# MyRollerShutter_rfm.net
KiCad netlist of a schematic drawn in EAGLE
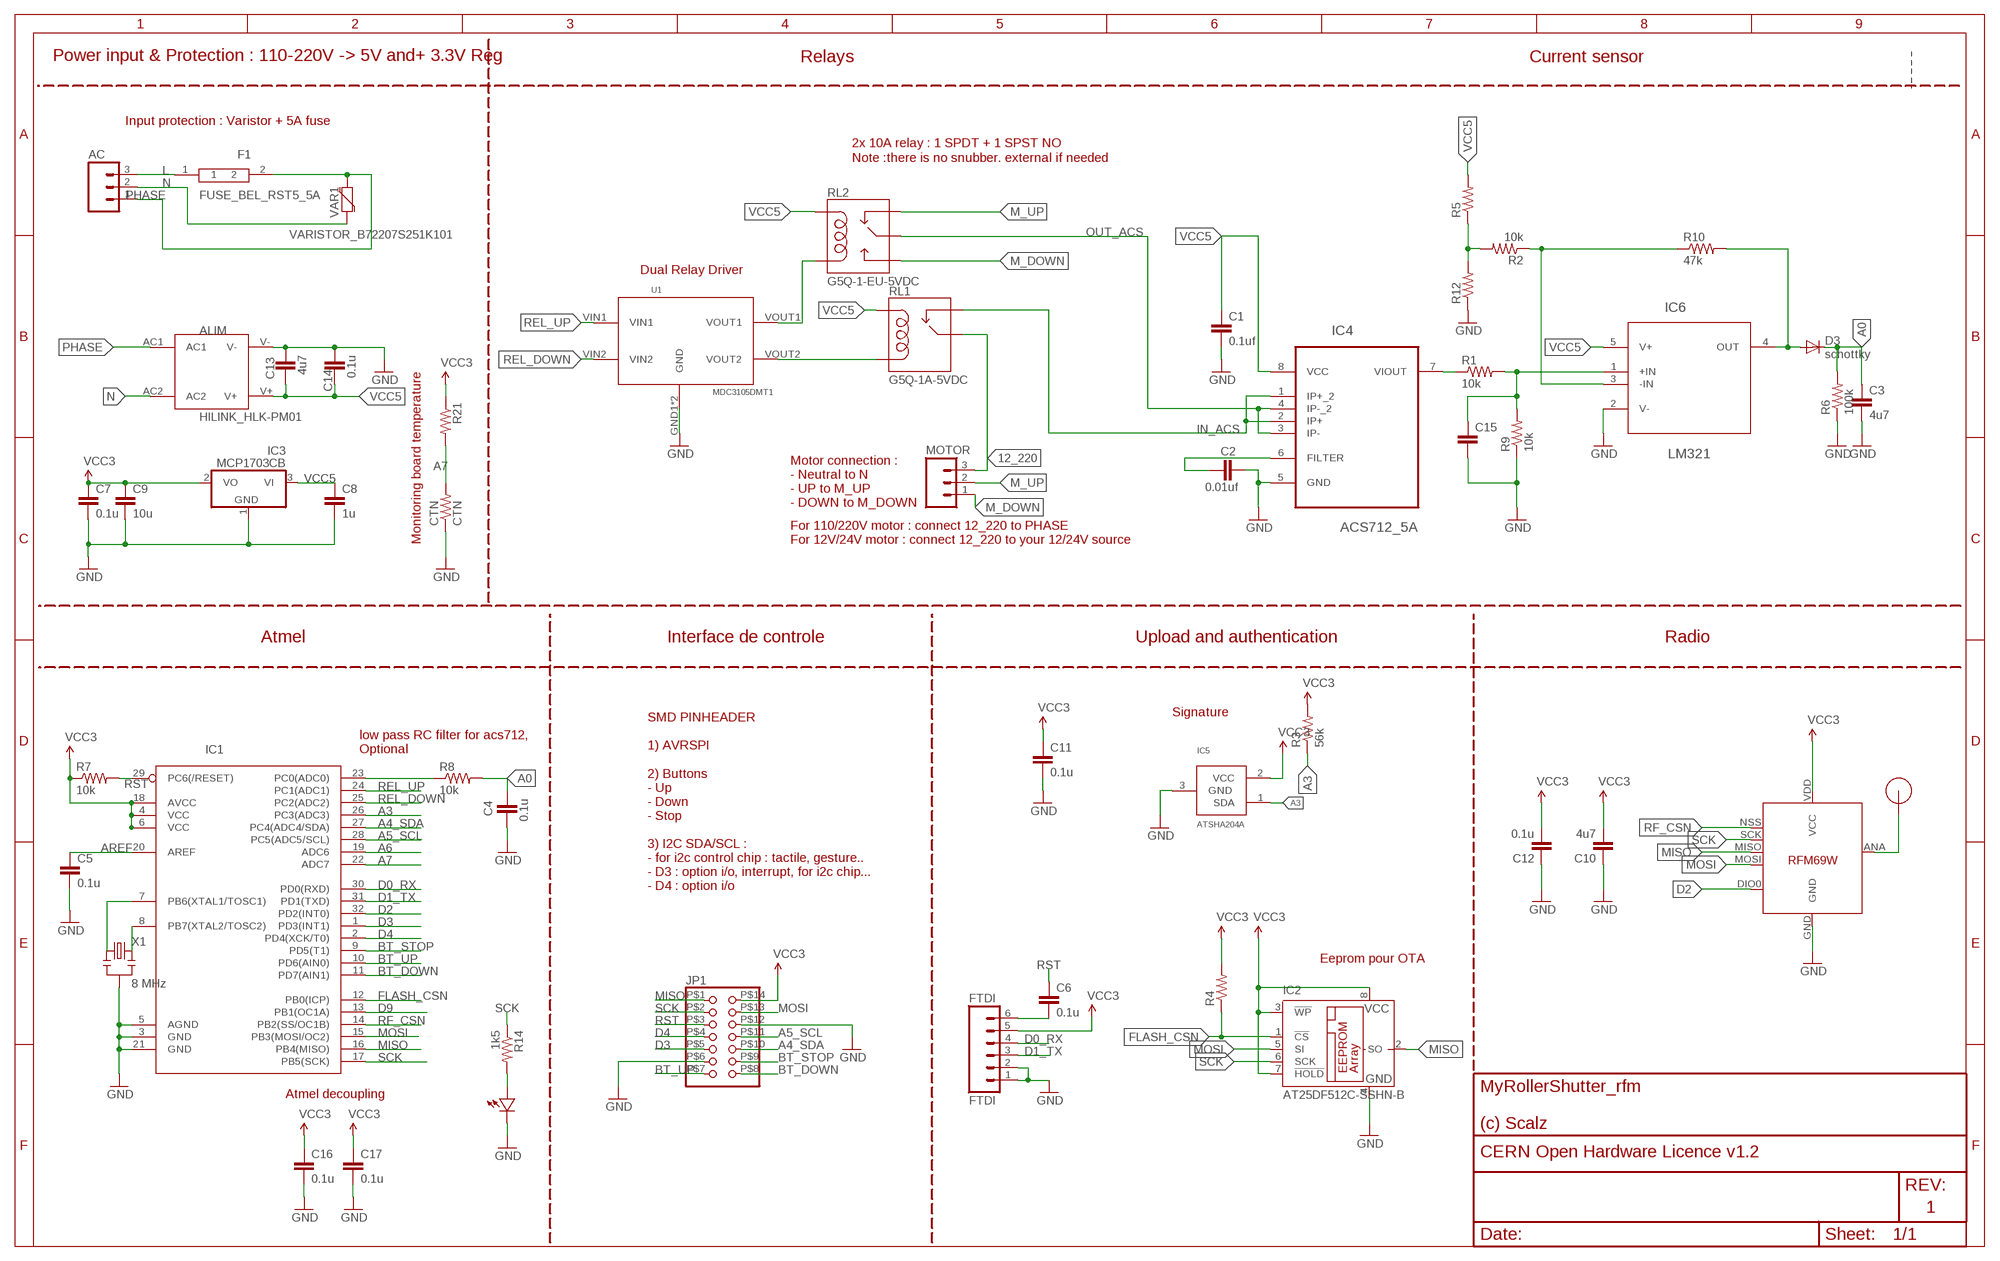
[diagram p0: schematic, sheet 1]

(export (version "E")
  (design (tool "Eeschema 10.0.6"))
  (components
    (comp (ref "AC")
      (value "M03-SCREW-5MM")
      (footprint "eagle-import:SCREWTERMINAL-5MM-3")
      (libsource (lib "eagle-import") (part "M03-SCREW-5MM"))
    )
    (comp (ref "ALIM")
      (value "HILINK_HLK-PM01")
      (footprint "eagle-import:HILINK_HLK-PM01")
      (libsource (lib "eagle-import") (part "HILINK_HLK-PM01"))
    )
    (comp (ref "ANT")
      (value "RFM12B_ANTENNA")
      (footprint "eagle-import:RFM12B-ANTENNA")
      (libsource (lib "eagle-import") (part "RFM12B_ANTENNA"))
    )
    (comp (ref "C1")
      (value "0.1uf")
      (footprint "eagle-import:0805-CAP")
      (libsource (lib "eagle-import") (part "CAP0805-CAP"))
    )
    (comp (ref "C2")
      (value "0.01uf")
      (footprint "eagle-import:0805-CAP")
      (libsource (lib "eagle-import") (part "CAP0805-CAP"))
    )
    (comp (ref "C3")
      (value "4u7")
      (footprint "eagle-import:0805-CAP")
      (libsource (lib "eagle-import") (part "CAP0805-CAP"))
    )
    (comp (ref "C4")
      (value "0.1u")
      (footprint "eagle-import:0805-CAP")
      (libsource (lib "eagle-import") (part "CAP0805-CAP"))
    )
    (comp (ref "C5")
      (value "0.1u")
      (footprint "eagle-import:0805-CAP")
      (libsource (lib "eagle-import") (part "CAP0805-CAP"))
    )
    (comp (ref "C6")
      (value "0.1u")
      (footprint "eagle-import:0805-CAP")
      (libsource (lib "eagle-import") (part "CAP0805-CAP"))
    )
    (comp (ref "C7")
      (value "0.1u")
      (footprint "eagle-import:0805-CAP")
      (libsource (lib "eagle-import") (part "CAP0805-CAP"))
    )
    (comp (ref "C8")
      (value "1u")
      (footprint "eagle-import:0805-CAP")
      (libsource (lib "eagle-import") (part "CAP0805-CAP"))
    )
    (comp (ref "C9")
      (value "10u")
      (footprint "eagle-import:0805-CAP")
      (libsource (lib "eagle-import") (part "CAP0805-CAP"))
    )
    (comp (ref "C10")
      (value "4u7")
      (footprint "eagle-import:0805-CAP")
      (libsource (lib "eagle-import") (part "CAP0805-CAP"))
    )
    (comp (ref "C11")
      (value "0.1u")
      (footprint "eagle-import:0805-CAP")
      (libsource (lib "eagle-import") (part "CAP0805-CAP"))
    )
    (comp (ref "C12")
      (value "0.1u")
      (footprint "eagle-import:0805-CAP")
      (libsource (lib "eagle-import") (part "CAP0805-CAP"))
    )
    (comp (ref "C13")
      (value "4u7")
      (footprint "eagle-import:0805-CAP")
      (libsource (lib "eagle-import") (part "CAP0805-CAP"))
    )
    (comp (ref "C14")
      (value "0.1u")
      (footprint "eagle-import:0805-CAP")
      (libsource (lib "eagle-import") (part "CAP0805-CAP"))
    )
    (comp (ref "C15")
      (value "CAP0805-CAP")
      (footprint "eagle-import:0805-CAP")
      (libsource (lib "eagle-import") (part "CAP0805-CAP"))
    )
    (comp (ref "C16")
      (value "0.1u")
      (footprint "eagle-import:0805-CAP")
      (libsource (lib "eagle-import") (part "CAP0805-CAP"))
    )
    (comp (ref "C17")
      (value "0.1u")
      (footprint "eagle-import:0805-CAP")
      (libsource (lib "eagle-import") (part "CAP0805-CAP"))
    )
    (comp (ref "CTN")
      (value "CTN")
      (footprint "eagle-import:0805-RES")
      (libsource (lib "eagle-import") (part "RESISTOR0805-RES"))
    )
    (comp (ref "D3")
      (value "schottky")
      (footprint "eagle-import:SOD-323")
      (libsource (lib "eagle-import") (part "DIODESOD"))
    )
    (comp (ref "D4")
      (value "LED0805")
      (footprint "eagle-import:0805-LED")
      (libsource (lib "eagle-import") (part "LED0805"))
    )
    (comp (ref "F1")
      (value "FUSE_BEL_RST5_5A")
      (footprint "eagle-import:FUSE_BEL_RST5_5A")
      (libsource (lib "eagle-import") (part "FUSE_BEL_RST5_5A"))
    )
    (comp (ref "FTDI")
      (value "FTDI")
      (footprint "eagle-import:1X06")
      (libsource (lib "eagle-import") (part "M06SIP"))
    )
    (comp (ref "IC1")
      (value "ATMega-328")
      (footprint "eagle-import:TQFP32-08")
      (libsource (lib "eagle-import") (part "ATMEGA168/328TQFP32"))
    )
    (comp (ref "IC2")
      (value "AT25DF512C-SSHN-B")
      (footprint "eagle-import:SO-08")
      (fields (field (name "MF") "MICROCHIP") (field (name "MPN") "25AA080/SN"))
      (libsource (lib "eagle-import") (part "25SNAA080"))
    )
    (comp (ref "IC3")
      (value "MCP1703CB")
      (footprint "eagle-import:SOT23")
      (libsource (lib "eagle-import") (part "MCP1703CB"))
    )
    (comp (ref "IC4")
      (value "ACS712_5A")
      (footprint "eagle-import:SOIC127P600X175-8N")
      (fields (field (name "MPN") "ACS712ELCTR-20A-T"))
      (libsource (lib "eagle-import") (part "ACS712ELCTR-20A-T"))
    )
    (comp (ref "IC5")
      (value "ATSHA204A")
      (footprint "eagle-import:SOT23")
      (libsource (lib "eagle-import") (part "ATSHA204A"))
    )
    (comp (ref "IC6")
      (value "LM321")
      (footprint "eagle-import:SOT95P285X120-5N")
      (fields (field (name "MPN") "LM321MF"))
      (libsource (lib "eagle-import") (part "LM321MF"))
    )
    (comp (ref "JP1")
      (value "PINHD-2X7")
      (footprint "eagle-import:2X07")
      (libsource (lib "eagle-import") (part "PINHD-2X7"))
    )
    (comp (ref "MOTOR")
      (value "M03-SCREW-5MM")
      (footprint "eagle-import:SCREWTERMINAL-5MM-3")
      (libsource (lib "eagle-import") (part "M03-SCREW-5MM"))
    )
    (comp (ref "R1")
      (value "10k")
      (footprint "eagle-import:0805-RES")
      (libsource (lib "eagle-import") (part "RESISTOR0805-RES"))
    )
    (comp (ref "R2")
      (value "10k")
      (footprint "eagle-import:0805-RES")
      (libsource (lib "eagle-import") (part "RESISTOR0805-RES"))
    )
    (comp (ref "R3")
      (value "56k")
      (footprint "eagle-import:0805-RES")
      (libsource (lib "eagle-import") (part "RESISTOR0805-RES"))
    )
    (comp (ref "R4")
      (value "RESISTOR0805-RES")
      (footprint "eagle-import:0805-RES")
      (libsource (lib "eagle-import") (part "RESISTOR0805-RES"))
    )
    (comp (ref "R5")
      (value "RESISTOR0805-RES")
      (footprint "eagle-import:0805-RES")
      (libsource (lib "eagle-import") (part "RESISTOR0805-RES"))
    )
    (comp (ref "R6")
      (value "100k")
      (footprint "eagle-import:0805-RES")
      (libsource (lib "eagle-import") (part "RESISTOR0805-RES"))
    )
    (comp (ref "R7")
      (value "10k")
      (footprint "eagle-import:0805-RES")
      (libsource (lib "eagle-import") (part "RESISTOR0805-RES"))
    )
    (comp (ref "R8")
      (value "10k")
      (footprint "eagle-import:0805-RES")
      (libsource (lib "eagle-import") (part "RESISTOR0805-RES"))
    )
    (comp (ref "R9")
      (value "10k")
      (footprint "eagle-import:0805-RES")
      (libsource (lib "eagle-import") (part "RESISTOR0805-RES"))
    )
    (comp (ref "R10")
      (value "47k")
      (footprint "eagle-import:0805-RES")
      (libsource (lib "eagle-import") (part "RESISTOR0805-RES"))
    )
    (comp (ref "R12")
      (value "RESISTOR0805-RES")
      (footprint "eagle-import:0805-RES")
      (libsource (lib "eagle-import") (part "RESISTOR0805-RES"))
    )
    (comp (ref "R14")
      (value "1k5")
      (footprint "eagle-import:0805-RES")
      (libsource (lib "eagle-import") (part "RESISTOR0805-RES"))
    )
    (comp (ref "R21")
      (value "RESISTOR0805-RES")
      (footprint "eagle-import:0805-RES")
      (libsource (lib "eagle-import") (part "RESISTOR0805-RES"))
    )
    (comp (ref "RFM69")
      (value "RFM69")
      (footprint "eagle-import:RFM69W-MINPADS")
      (libsource (lib "eagle-import") (part "RFM69"))
    )
    (comp (ref "RL1")
      (value "G5Q-1A-5VDC")
      (footprint "eagle-import:G5Q_SINGLE")
      (libsource (lib "eagle-import") (part "G5Q_SINGLE"))
    )
    (comp (ref "RL2")
      (value "G5Q-1-EU-5VDC")
      (footprint "eagle-import:RELAY-G5Q")
      (libsource (lib "eagle-import") (part "RELAYPTH"))
    )
    (comp (ref "U1")
      (value "MDC3105DMT1")
      (footprint "eagle-import:MDC3105DMT1")
      (libsource (lib "eagle-import") (part "MDC3105DMT1"))
    )
    (comp (ref "VAR1")
      (value "VARISTOR_B72207S251K101")
      (footprint "eagle-import:VARISTOR_B72207S251K101")
      (libsource (lib "eagle-import") (part "VARISTOR_B72207S251K101"))
    )
    (comp (ref "X1")
      (value "8 MHz")
      (footprint "eagle-import:RESONATOR-SMD")
      (libsource (lib "eagle-import") (part "RESONATORSMD"))
    )
  )
  (nets
    (net (code "1") (name "/A4_SDA") (class "Default")
      (node (ref "IC1") (pin "27") (pinfunction "PC4(ADC4/SDA)_27") (pintype "bidirectional"))
      (node (ref "JP1") (pin "P$10") (pinfunction "10_P$10") (pintype "passive"))
    )
    (net (code "2") (name "/A5_SCL") (class "Default")
      (node (ref "IC1") (pin "28") (pinfunction "PC5(ADC5/SCL)_28") (pintype "bidirectional"))
      (node (ref "JP1") (pin "P$11") (pinfunction "8_P$11") (pintype "passive"))
    )
    (net (code "3") (name "/A6") (class "Default")
      (node (ref "IC1") (pin "19") (pinfunction "ADC6_19") (pintype "bidirectional"))
    )
    (net (code "4") (name "/A7") (class "Default")
      (node (ref "CTN") (pin "2") (pinfunction "2_2") (pintype "passive"))
      (node (ref "IC1") (pin "22") (pinfunction "ADC7_22") (pintype "bidirectional"))
      (node (ref "R21") (pin "2") (pinfunction "2_2") (pintype "passive"))
    )
    (net (code "5") (name "/AREF") (class "Default")
      (node (ref "C5") (pin "1") (pinfunction "1_1") (pintype "passive"))
      (node (ref "IC1") (pin "20") (pinfunction "AREF_20") (pintype "bidirectional"))
    )
    (net (code "6") (name "/BT_DOWN") (class "Default")
      (node (ref "IC1") (pin "11") (pinfunction "PD7(AIN1)_11") (pintype "bidirectional"))
      (node (ref "JP1") (pin "P$8") (pinfunction "14_P$8") (pintype "passive"))
    )
    (net (code "7") (name "/BT_STOP") (class "Default")
      (node (ref "IC1") (pin "9") (pinfunction "PD5(T1)_9") (pintype "bidirectional"))
      (node (ref "JP1") (pin "P$9") (pinfunction "12_P$9") (pintype "passive"))
    )
    (net (code "8") (name "/BT_UP") (class "Default")
      (node (ref "IC1") (pin "10") (pinfunction "PD6(AIN0)_10") (pintype "bidirectional"))
      (node (ref "JP1") (pin "P$7") (pinfunction "13_P$7") (pintype "passive"))
    )
    (net (code "9") (name "/D0_RX") (class "Default")
      (node (ref "FTDI") (pin "4") (pinfunction "4_4") (pintype "passive"))
      (node (ref "IC1") (pin "30") (pinfunction "PD0(RXD)_30") (pintype "bidirectional"))
    )
    (net (code "10") (name "/D1_TX") (class "Default")
      (node (ref "FTDI") (pin "3") (pinfunction "3_3") (pintype "passive"))
      (node (ref "IC1") (pin "31") (pinfunction "PD1(TXD)_31") (pintype "bidirectional"))
    )
    (net (code "11") (name "/D3") (class "Default")
      (node (ref "IC1") (pin "1") (pinfunction "PD3(INT1)_1") (pintype "bidirectional"))
      (node (ref "JP1") (pin "P$5") (pinfunction "9_P$5") (pintype "passive"))
    )
    (net (code "12") (name "/D4") (class "Default")
      (node (ref "IC1") (pin "2") (pinfunction "PD4(XCK/T0)_2") (pintype "bidirectional"))
      (node (ref "JP1") (pin "P$4") (pinfunction "7_P$4") (pintype "passive"))
    )
    (net (code "13") (name "/D9") (class "Default")
      (node (ref "IC1") (pin "13") (pinfunction "PB1(OC1A)_13") (pintype "bidirectional"))
    )
    (net (code "14") (name "/IN_ACS") (class "Default")
      (node (ref "IC4") (pin "1") (pinfunction "IP+_2_1") (pintype "input"))
      (node (ref "IC4") (pin "2") (pinfunction "IP+_2") (pintype "input"))
      (node (ref "RL1") (pin "3") (pinfunction "NC_3") (pintype "bidirectional"))
    )
    (net (code "15") (name "/L") (class "Default")
      (node (ref "AC") (pin "3") (pinfunction "3_3") (pintype "passive"))
      (node (ref "F1") (pin "1") (pinfunction "1_1") (pintype "bidirectional"))
    )
    (net (code "16") (name "/OUT_ACS") (class "Default")
      (node (ref "IC4") (pin "3") (pinfunction "IP-_3") (pintype "input"))
      (node (ref "IC4") (pin "4") (pinfunction "IP-_2_4") (pintype "input"))
      (node (ref "RL2") (pin "2") (pinfunction "MAIN_2") (pintype "bidirectional"))
    )
    (net (code "17") (name "/RST") (class "Default")
      (node (ref "C6") (pin "1") (pinfunction "1_1") (pintype "passive"))
      (node (ref "IC1") (pin "29") (pinfunction "PC6(/RESET)_29") (pintype "bidirectional"))
      (node (ref "JP1") (pin "P$3") (pinfunction "5_P$3") (pintype "passive"))
      (node (ref "R7") (pin "2") (pinfunction "2_2") (pintype "passive"))
    )
    (net (code "18") (name "12_220") (class "Default")
      (node (ref "MOTOR") (pin "3") (pinfunction "3_3") (pintype "passive"))
      (node (ref "RL1") (pin "2") (pinfunction "MAIN_2") (pintype "bidirectional"))
    )
    (net (code "19") (name "A0") (class "Default")
      (node (ref "C3") (pin "1") (pinfunction "1_1") (pintype "passive"))
      (node (ref "C4") (pin "2") (pinfunction "2_2") (pintype "passive"))
      (node (ref "D3") (pin "1") (pinfunction "C_1") (pintype "passive"))
      (node (ref "R6") (pin "2") (pinfunction "2_2") (pintype "passive"))
      (node (ref "R8") (pin "2") (pinfunction "2_2") (pintype "passive"))
    )
    (net (code "20") (name "A3") (class "Default")
      (node (ref "IC1") (pin "26") (pinfunction "PC3(ADC3)_26") (pintype "bidirectional"))
      (node (ref "IC5") (pin "1") (pinfunction "SDA_1") (pintype "bidirectional"))
      (node (ref "R3") (pin "1") (pinfunction "1_1") (pintype "passive"))
    )
    (net (code "21") (name "D2") (class "Default")
      (node (ref "IC1") (pin "32") (pinfunction "PD2(INT0)_32") (pintype "bidirectional"))
      (node (ref "RFM69") (pin "DIO0") (pinfunction "DIO0_DIO0") (pintype "open_collector"))
    )
    (net (code "22") (name "FLASH_CSN") (class "Default")
      (node (ref "IC1") (pin "12") (pinfunction "PB0(ICP)_12") (pintype "bidirectional"))
      (node (ref "IC2") (pin "1") (pinfunction "~{CS}_1") (pintype "input"))
      (node (ref "R4") (pin "1") (pinfunction "1_1") (pintype "passive"))
    )
    (net (code "23") (name "GND") (class "Default")
      (node (ref "ALIM") (pin "V-") (pinfunction "V-_V-") (pintype "bidirectional"))
      (node (ref "C1") (pin "2") (pinfunction "2_2") (pintype "passive"))
      (node (ref "C10") (pin "1") (pinfunction "1_1") (pintype "passive"))
      (node (ref "C11") (pin "2") (pinfunction "2_2") (pintype "passive"))
      (node (ref "C12") (pin "1") (pinfunction "1_1") (pintype "passive"))
      (node (ref "C13") (pin "2") (pinfunction "2_2") (pintype "passive"))
      (node (ref "C14") (pin "2") (pinfunction "2_2") (pintype "passive"))
      (node (ref "C15") (pin "2") (pinfunction "2_2") (pintype "passive"))
      (node (ref "C16") (pin "2") (pinfunction "2_2") (pintype "passive"))
      (node (ref "C17") (pin "2") (pinfunction "2_2") (pintype "passive"))
      (node (ref "C2") (pin "2") (pinfunction "2_2") (pintype "passive"))
      (node (ref "C3") (pin "2") (pinfunction "2_2") (pintype "passive"))
      (node (ref "C4") (pin "1") (pinfunction "1_1") (pintype "passive"))
      (node (ref "C5") (pin "2") (pinfunction "2_2") (pintype "passive"))
      (node (ref "C7") (pin "2") (pinfunction "2_2") (pintype "passive"))
      (node (ref "C8") (pin "2") (pinfunction "2_2") (pintype "passive"))
      (node (ref "C9") (pin "2") (pinfunction "2_2") (pintype "passive"))
      (node (ref "CTN") (pin "1") (pinfunction "1_1") (pintype "passive"))
      (node (ref "D4") (pin "MINUS") (pinfunction "MINUS_MINUS") (pintype "passive"))
      (node (ref "FTDI") (pin "1") (pinfunction "1_1") (pintype "passive"))
      (node (ref "FTDI") (pin "2") (pinfunction "2_2") (pintype "passive"))
      (node (ref "IC1") (pin "21") (pinfunction "GND_21") (pintype "bidirectional"))
      (node (ref "IC1") (pin "3") (pinfunction "GND_3") (pintype "bidirectional"))
      (node (ref "IC1") (pin "5") (pinfunction "AGND_5") (pintype "bidirectional"))
      (node (ref "IC2") (pin "4") (pinfunction "GND_4") (pintype "power_in"))
      (node (ref "IC3") (pin "1") (pinfunction "GND_1") (pintype "passive"))
      (node (ref "IC4") (pin "5") (pinfunction "GND_5") (pintype "passive"))
      (node (ref "IC5") (pin "3") (pinfunction "GND_3") (pintype "bidirectional"))
      (node (ref "IC6") (pin "2") (pinfunction "V-_2") (pintype "power_in"))
      (node (ref "JP1") (pin "P$12") (pinfunction "6_P$12") (pintype "passive"))
      (node (ref "JP1") (pin "P$6") (pinfunction "11_P$6") (pintype "passive"))
      (node (ref "R12") (pin "1") (pinfunction "1_1") (pintype "passive"))
      (node (ref "R6") (pin "1") (pinfunction "1_1") (pintype "passive"))
      (node (ref "R9") (pin "1") (pinfunction "1_1") (pintype "passive"))
      (node (ref "RFM69") (pin "GND") (pinfunction "GND_GND") (pintype "power_in"))
      (node (ref "U1") (pin "GND1") (pinfunction "GND_GND1") (pintype "bidirectional"))
      (node (ref "U1") (pin "GND2") (pinfunction "GND_GND2") (pintype "bidirectional"))
      (node (ref "X1") (pin "2") (pinfunction "2_2") (pintype "passive"))
    )
    (net (code "24") (name "MISO") (class "Default")
      (node (ref "IC1") (pin "16") (pinfunction "PB4(MISO)_16") (pintype "bidirectional"))
      (node (ref "IC2") (pin "2") (pinfunction "SO_2") (pintype "bidirectional"))
      (node (ref "JP1") (pin "P$1") (pinfunction "1_P$1") (pintype "passive"))
      (node (ref "RFM69") (pin "MISO") (pinfunction "MISO_MISO") (pintype "input"))
    )
    (net (code "25") (name "MOSI") (class "Default")
      (node (ref "IC1") (pin "15") (pinfunction "PB3(MOSI/OC2)_15") (pintype "bidirectional"))
      (node (ref "IC2") (pin "5") (pinfunction "SI_5") (pintype "input"))
      (node (ref "JP1") (pin "P$13") (pinfunction "4_P$13") (pintype "passive"))
      (node (ref "RFM69") (pin "MOSI") (pinfunction "MOSI_MOSI") (pintype "output"))
    )
    (net (code "26") (name "M_DOWN") (class "Default")
      (node (ref "MOTOR") (pin "1") (pinfunction "1_1") (pintype "passive"))
      (node (ref "RL2") (pin "3") (pinfunction "NO_3") (pintype "bidirectional"))
    )
    (net (code "27") (name "M_UP") (class "Default")
      (node (ref "MOTOR") (pin "2") (pinfunction "2_2") (pintype "passive"))
      (node (ref "RL2") (pin "4") (pinfunction "NC_4") (pintype "bidirectional"))
    )
    (net (code "28") (name "N") (class "Default")
      (node (ref "AC") (pin "2") (pinfunction "2_2") (pintype "passive"))
      (node (ref "ALIM") (pin "AC2") (pinfunction "AC2_AC2") (pintype "bidirectional"))
      (node (ref "VAR1") (pin "1") (pinfunction "1_1") (pintype "passive"))
    )
    (net (code "29") (name "Net-(ANT-1)") (class "Default")
      (node (ref "ANT") (pin "P$1") (pinfunction "1_P$1") (pintype "bidirectional"))
      (node (ref "RFM69") (pin "ANA") (pinfunction "ANT_ANA") (pintype "passive"))
    )
    (net (code "30") (name "Net-(C6-Pad2)") (class "Default")
      (node (ref "C6") (pin "2") (pinfunction "2_2") (pintype "passive"))
      (node (ref "FTDI") (pin "6") (pinfunction "6_6") (pintype "passive"))
    )
    (net (code "31") (name "Net-(D3-A)") (class "Default")
      (node (ref "D3") (pin "2") (pinfunction "A_2") (pintype "passive"))
      (node (ref "IC6") (pin "4") (pinfunction "OUT_4") (pintype "output"))
      (node (ref "R10") (pin "2") (pinfunction "2_2") (pintype "passive"))
    )
    (net (code "32") (name "Net-(D4-PadPLUS)") (class "Default")
      (node (ref "D4") (pin "PLUS") (pinfunction "PLUS_PLUS") (pintype "passive"))
      (node (ref "R14") (pin "2") (pinfunction "2_2") (pintype "passive"))
    )
    (net (code "33") (name "Net-(IC1-PB6(XTAL1{slash}TOSC1))") (class "Default")
      (node (ref "IC1") (pin "7") (pinfunction "PB6(XTAL1/TOSC1)_7") (pintype "bidirectional"))
      (node (ref "X1") (pin "1") (pinfunction "1_1") (pintype "passive"))
    )
    (net (code "34") (name "Net-(IC1-PB7(XTAL2{slash}TOSC2))") (class "Default")
      (node (ref "IC1") (pin "8") (pinfunction "PB7(XTAL2/TOSC2)_8") (pintype "bidirectional"))
      (node (ref "X1") (pin "3") (pinfunction "3_3") (pintype "passive"))
    )
    (net (code "35") (name "Net-(IC1-PC0(ADC0))") (class "Default")
      (node (ref "IC1") (pin "23") (pinfunction "PC0(ADC0)_23") (pintype "bidirectional"))
      (node (ref "R8") (pin "1") (pinfunction "1_1") (pintype "passive"))
    )
    (net (code "36") (name "Net-(IC4-FILTER)") (class "Default")
      (node (ref "C2") (pin "1") (pinfunction "1_1") (pintype "passive"))
      (node (ref "IC4") (pin "6") (pinfunction "FILTER_6") (pintype "input"))
    )
    (net (code "37") (name "Net-(IC4-VIOUT)") (class "Default")
      (node (ref "IC4") (pin "7") (pinfunction "VIOUT_7") (pintype "output"))
      (node (ref "R1") (pin "1") (pinfunction "1_1") (pintype "passive"))
    )
    (net (code "38") (name "Net-(IC6-+IN)") (class "Default")
      (node (ref "C15") (pin "1") (pinfunction "1_1") (pintype "passive"))
      (node (ref "IC6") (pin "1") (pinfunction "+IN_1") (pintype "input"))
      (node (ref "R1") (pin "2") (pinfunction "2_2") (pintype "passive"))
      (node (ref "R9") (pin "2") (pinfunction "2_2") (pintype "passive"))
    )
    (net (code "39") (name "Net-(IC6--IN)") (class "Default")
      (node (ref "IC6") (pin "3") (pinfunction "-IN_3") (pintype "input"))
      (node (ref "R10") (pin "1") (pinfunction "1_1") (pintype "passive"))
      (node (ref "R2") (pin "1") (pinfunction "1_1") (pintype "passive"))
    )
    (net (code "40") (name "Net-(R12-Pad2)") (class "Default")
      (node (ref "R12") (pin "2") (pinfunction "2_2") (pintype "passive"))
      (node (ref "R2") (pin "2") (pinfunction "2_2") (pintype "passive"))
      (node (ref "R5") (pin "1") (pinfunction "1_1") (pintype "passive"))
    )
    (net (code "41") (name "Net-(RL1-COIL2)") (class "Default")
      (node (ref "RL1") (pin "5") (pinfunction "COIL2_5") (pintype "bidirectional"))
      (node (ref "U1") (pin "VOUT2") (pinfunction "VOUT2_VOUT2") (pintype "bidirectional"))
    )
    (net (code "42") (name "Net-(RL2-COIL2)") (class "Default")
      (node (ref "RL2") (pin "1") (pinfunction "COIL2_1") (pintype "bidirectional"))
      (node (ref "U1") (pin "VOUT1") (pinfunction "VOUT1_VOUT1") (pintype "bidirectional"))
    )
    (net (code "43") (name "PHASE") (class "Default")
      (node (ref "AC") (pin "1") (pinfunction "1_1") (pintype "passive"))
      (node (ref "ALIM") (pin "AC1") (pinfunction "AC1_AC1") (pintype "bidirectional"))
      (node (ref "F1") (pin "2") (pinfunction "2_2") (pintype "bidirectional"))
      (node (ref "VAR1") (pin "2") (pinfunction "2_2") (pintype "passive"))
    )
    (net (code "44") (name "REL_DOWN") (class "Default")
      (node (ref "IC1") (pin "25") (pinfunction "PC2(ADC2)_25") (pintype "bidirectional"))
      (node (ref "U1") (pin "VIN2") (pinfunction "VIN2_VIN2") (pintype "bidirectional"))
    )
    (net (code "45") (name "REL_UP") (class "Default")
      (node (ref "IC1") (pin "24") (pinfunction "PC1(ADC1)_24") (pintype "bidirectional"))
      (node (ref "U1") (pin "VIN1") (pinfunction "VIN1_VIN1") (pintype "bidirectional"))
    )
    (net (code "46") (name "RF_CSN") (class "Default")
      (node (ref "IC1") (pin "14") (pinfunction "PB2(SS/OC1B)_14") (pintype "bidirectional"))
      (node (ref "RFM69") (pin "NSS") (pinfunction "SEL_NSS") (pintype "input"))
    )
    (net (code "47") (name "SCK") (class "Default")
      (node (ref "IC1") (pin "17") (pinfunction "PB5(SCK)_17") (pintype "bidirectional"))
      (node (ref "IC2") (pin "6") (pinfunction "SCK_6") (pintype "input"))
      (node (ref "JP1") (pin "P$2") (pinfunction "3_P$2") (pintype "passive"))
      (node (ref "R14") (pin "1") (pinfunction "1_1") (pintype "passive"))
      (node (ref "RFM69") (pin "SCK") (pinfunction "SCK_SCK") (pintype "input"))
    )
    (net (code "48") (name "VCC3") (class "Default")
      (node (ref "C10") (pin "2") (pinfunction "2_2") (pintype "passive"))
      (node (ref "C11") (pin "1") (pinfunction "1_1") (pintype "passive"))
      (node (ref "C12") (pin "2") (pinfunction "2_2") (pintype "passive"))
      (node (ref "C16") (pin "1") (pinfunction "1_1") (pintype "passive"))
      (node (ref "C17") (pin "1") (pinfunction "1_1") (pintype "passive"))
      (node (ref "C7") (pin "1") (pinfunction "1_1") (pintype "passive"))
      (node (ref "C9") (pin "1") (pinfunction "1_1") (pintype "passive"))
      (node (ref "FTDI") (pin "5") (pinfunction "5_5") (pintype "passive"))
      (node (ref "IC1") (pin "18") (pinfunction "AVCC_18") (pintype "bidirectional"))
      (node (ref "IC1") (pin "4") (pinfunction "VCC_4") (pintype "bidirectional"))
      (node (ref "IC1") (pin "6") (pinfunction "VCC_6") (pintype "bidirectional"))
      (node (ref "IC2") (pin "3") (pinfunction "~{WP}_3") (pintype "input"))
      (node (ref "IC2") (pin "7") (pinfunction "~{HOLD}_7") (pintype "input"))
      (node (ref "IC2") (pin "8") (pinfunction "VCC_8") (pintype "power_in"))
      (node (ref "IC3") (pin "2") (pinfunction "VO_2") (pintype "passive"))
      (node (ref "IC5") (pin "2") (pinfunction "VCC_2") (pintype "bidirectional"))
      (node (ref "JP1") (pin "P$14") (pinfunction "2_P$14") (pintype "passive"))
      (node (ref "R21") (pin "1") (pinfunction "1_1") (pintype "passive"))
      (node (ref "R3") (pin "2") (pinfunction "2_2") (pintype "passive"))
      (node (ref "R4") (pin "2") (pinfunction "2_2") (pintype "passive"))
      (node (ref "R7") (pin "1") (pinfunction "1_1") (pintype "passive"))
      (node (ref "RFM69") (pin "VDD") (pinfunction "VCC_VDD") (pintype "power_in"))
    )
    (net (code "49") (name "VCC5") (class "Default")
      (node (ref "ALIM") (pin "V+") (pinfunction "V+_V+") (pintype "bidirectional"))
      (node (ref "C1") (pin "1") (pinfunction "1_1") (pintype "passive"))
      (node (ref "C13") (pin "1") (pinfunction "1_1") (pintype "passive"))
      (node (ref "C14") (pin "1") (pinfunction "1_1") (pintype "passive"))
      (node (ref "C8") (pin "1") (pinfunction "1_1") (pintype "passive"))
      (node (ref "IC3") (pin "3") (pinfunction "VI_3") (pintype "input"))
      (node (ref "IC4") (pin "8") (pinfunction "VCC_8") (pintype "power_in"))
      (node (ref "IC6") (pin "5") (pinfunction "V+_5") (pintype "power_in"))
      (node (ref "R5") (pin "2") (pinfunction "2_2") (pintype "passive"))
      (node (ref "RL1") (pin "1") (pinfunction "COIL1_1") (pintype "bidirectional"))
      (node (ref "RL2") (pin "5") (pinfunction "COIL1_5") (pintype "bidirectional"))
    )
  )
)
